# G6S-2G-Y.net
KiCad netlist of a schematic drawn in EAGLE
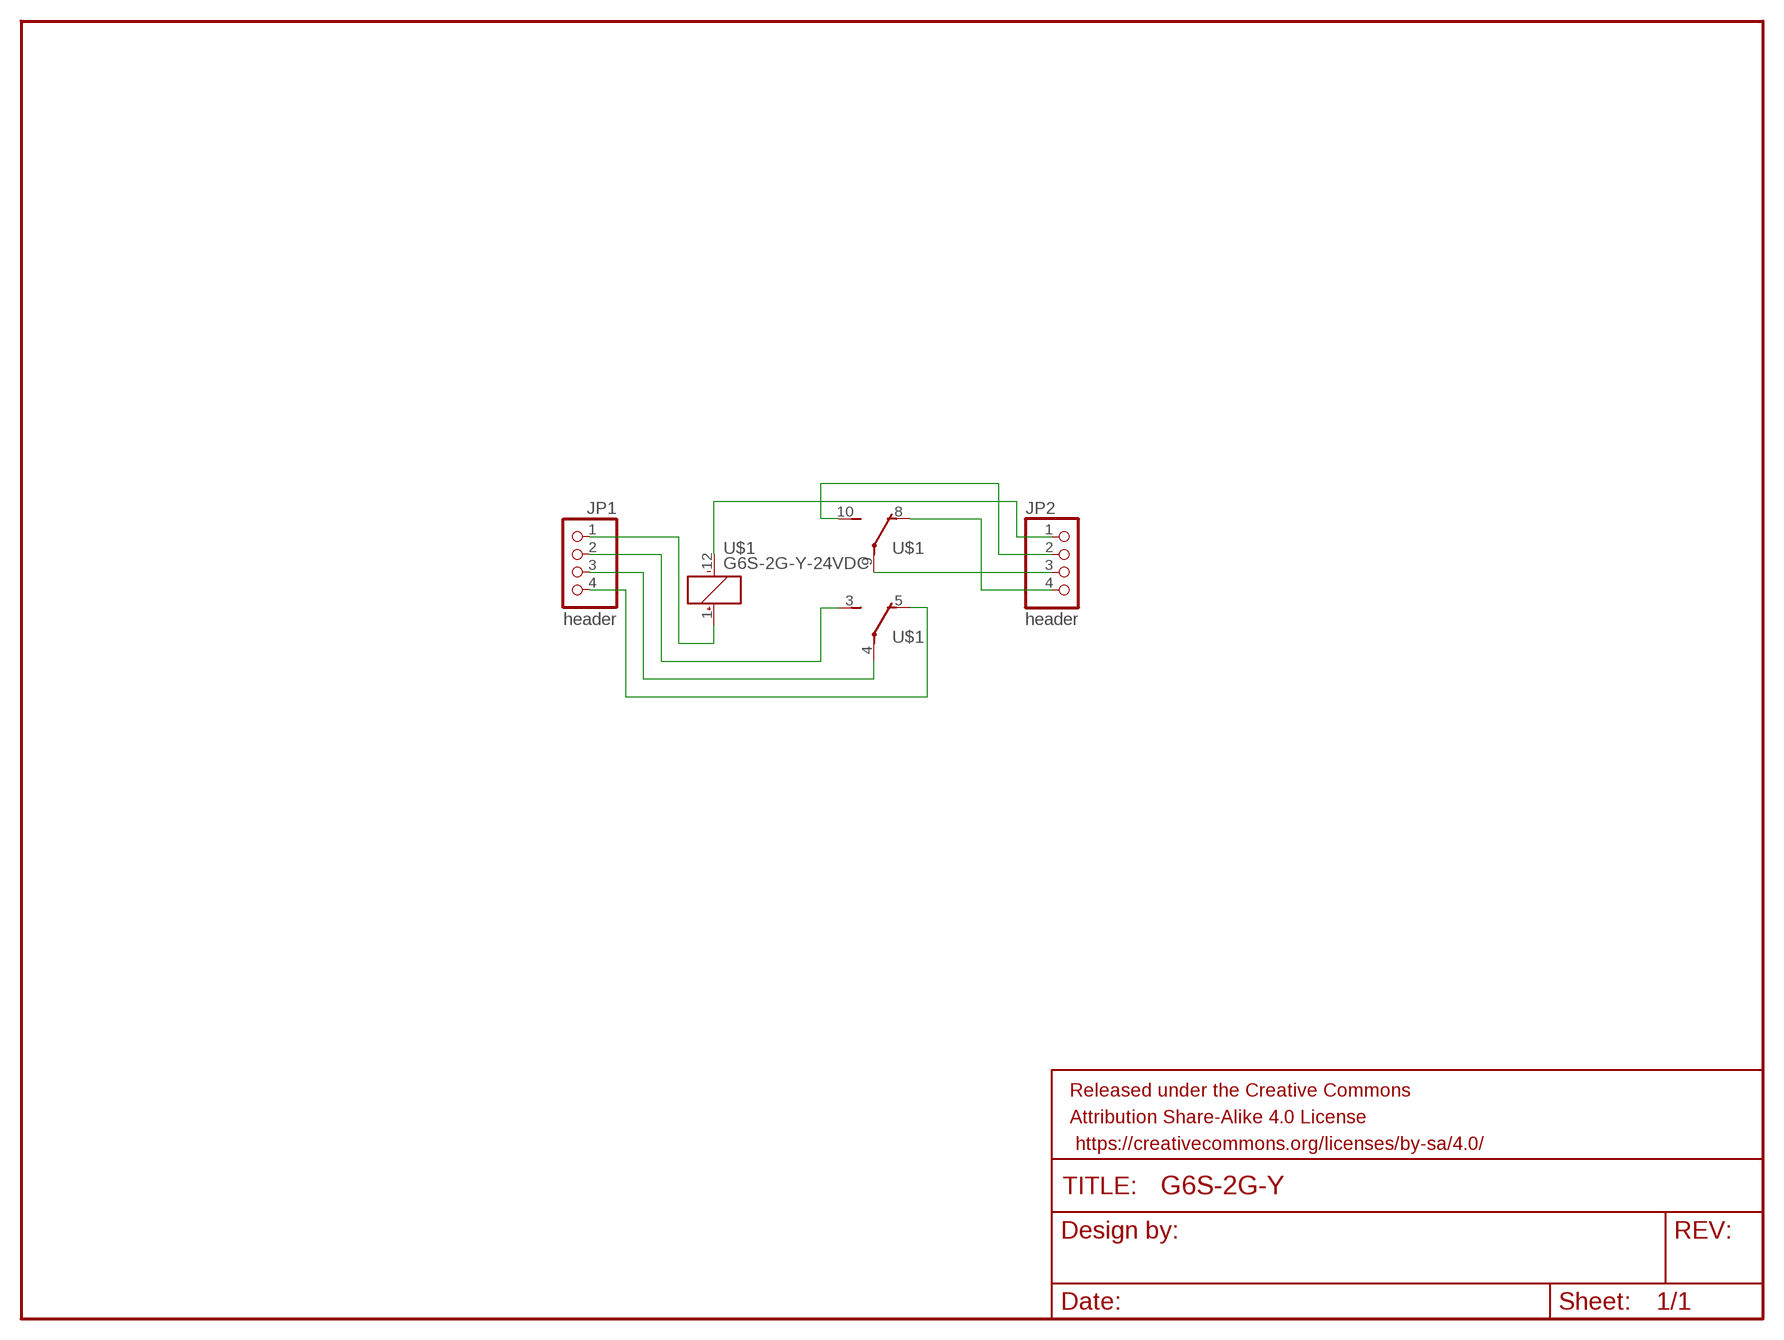
[diagram p0: schematic, sheet 1]

(export (version "E")
  (design (tool "Eeschema 10.0.6"))
  (components
    (comp (ref "FRAME1")
      (value "FRAME-LETTER")
      (footprint "eagle-import:CREATIVE_COMMONS")
      (libsource (lib "eagle-import") (part "FRAME-LETTER"))
    )
    (comp (ref "JP1")
      (value "header")
      (footprint "eagle-import:1X04")
      (libsource (lib "eagle-import") (part "PINHD-1X4"))
    )
    (comp (ref "JP2")
      (value "header")
      (footprint "eagle-import:1X04")
      (libsource (lib "eagle-import") (part "PINHD-1X4"))
    )
    (comp (ref "U$1")
      (value "G6S-2G-Y-24VDC")
      (footprint "eagle-import:G6S-2G-Y-24VDC")
      (libsource (lib "eagle-import") (part "G6S-2G-Y-24VDC"))
    )
  )
  (nets
    (net (code "1") (name "Net-(U$1A-+)") (class "Default")
      (node (ref "JP1") (pin "1") (pinfunction "1_1") (pintype "passive"))
      (node (ref "U$1") (pin "1") (pinfunction "+_1") (pintype "passive"))
    )
    (net (code "2") (name "Net-(U$1A--)") (class "Default")
      (node (ref "JP2") (pin "1") (pinfunction "1_1") (pintype "passive"))
      (node (ref "U$1") (pin "12") (pinfunction "-_12") (pintype "passive"))
    )
    (net (code "3") (name "Net-(U$1B-COM)") (class "Default")
      (node (ref "JP2") (pin "3") (pinfunction "3_3") (pintype "passive"))
      (node (ref "U$1") (pin "9") (pinfunction "COM_9") (pintype "passive"))
    )
    (net (code "4") (name "Net-(U$1B-NC)") (class "Default")
      (node (ref "JP2") (pin "4") (pinfunction "4_4") (pintype "passive"))
      (node (ref "U$1") (pin "8") (pinfunction "NC_8") (pintype "passive"))
    )
    (net (code "5") (name "Net-(U$1B-NO)") (class "Default")
      (node (ref "JP2") (pin "2") (pinfunction "2_2") (pintype "passive"))
      (node (ref "U$1") (pin "10") (pinfunction "NO_10") (pintype "passive"))
    )
    (net (code "6") (name "Net-(U$1C-COM)") (class "Default")
      (node (ref "JP1") (pin "3") (pinfunction "3_3") (pintype "passive"))
      (node (ref "U$1") (pin "4") (pinfunction "COM_4") (pintype "passive"))
    )
    (net (code "7") (name "Net-(U$1C-NC)") (class "Default")
      (node (ref "JP1") (pin "4") (pinfunction "4_4") (pintype "passive"))
      (node (ref "U$1") (pin "5") (pinfunction "NC_5") (pintype "passive"))
    )
    (net (code "8") (name "Net-(U$1C-NO)") (class "Default")
      (node (ref "JP1") (pin "2") (pinfunction "2_2") (pintype "passive"))
      (node (ref "U$1") (pin "3") (pinfunction "NO_3") (pintype "passive"))
    )
  )
)
